# Adafruit_Circuit_Playground_Express.net
KiCad netlist of a schematic drawn in EAGLE
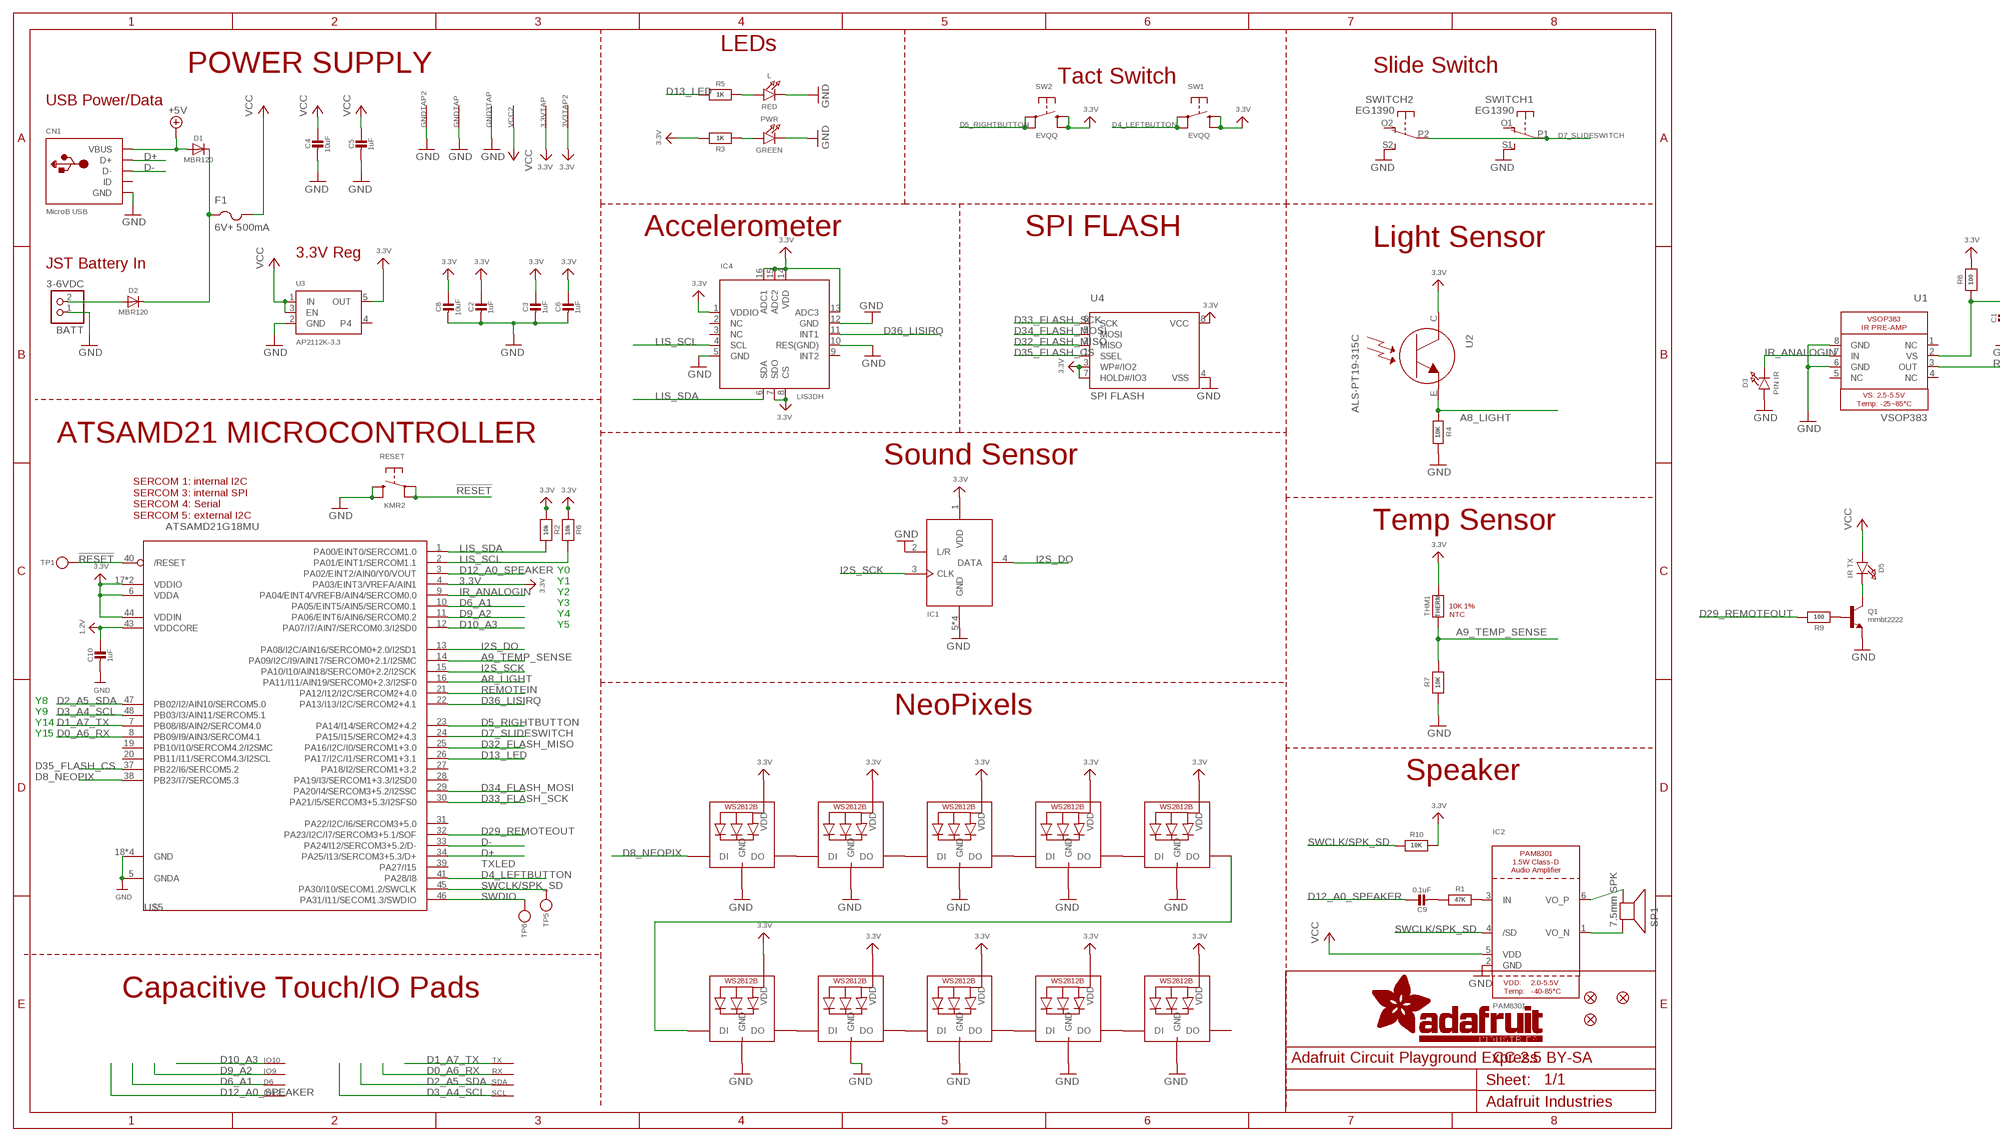
[diagram p0: schematic, sheet 1, part 1 of 2]
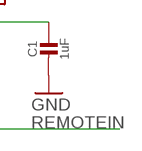
[diagram p1: schematic, sheet 1, part 2 of 2]

(export (version "E")
  (design (tool "Eeschema 10.0.6"))
  (components
    (comp (ref "3.3VTAP")
      (value "SEWTAP-ALLIGATOR")
      (footprint "eagle-import:SEWALLI")
      (libsource (lib "eagle-import") (part "SEWTAP-ALLIGATOR"))
    )
    (comp (ref "3V3TAP2")
      (value "SEWTAP-ALLIGATOR")
      (footprint "eagle-import:SEWALLI")
      (libsource (lib "eagle-import") (part "SEWTAP-ALLIGATOR"))
    )
    (comp (ref "BATT")
      (value "3-6VDC")
      (footprint "eagle-import:JSTPH2")
      (libsource (lib "eagle-import") (part "CON_JST_PH_2PIN"))
    )
    (comp (ref "C1")
      (value "1uF")
      (footprint "eagle-import:0603-NO")
      (libsource (lib "eagle-import") (part "CAP_CERAMIC0603_NO"))
    )
    (comp (ref "C2")
      (value "1uF")
      (footprint "eagle-import:0603-NO")
      (libsource (lib "eagle-import") (part "CAP_CERAMIC0603_NO"))
    )
    (comp (ref "C3")
      (value "1uF")
      (footprint "eagle-import:0603-NO")
      (libsource (lib "eagle-import") (part "CAP_CERAMIC0603_NO"))
    )
    (comp (ref "C4")
      (value "10uF")
      (footprint "eagle-import:0805-NO")
      (libsource (lib "eagle-import") (part "CAP_CERAMIC0805-NOOUTLINE"))
    )
    (comp (ref "C5")
      (value "1uF")
      (footprint "eagle-import:0603-NO")
      (libsource (lib "eagle-import") (part "CAP_CERAMIC0603_NO"))
    )
    (comp (ref "C6")
      (value "1uF")
      (footprint "eagle-import:0603-NO")
      (libsource (lib "eagle-import") (part "CAP_CERAMIC0603_NO"))
    )
    (comp (ref "C8")
      (value "10uF")
      (footprint "eagle-import:0805-NO")
      (libsource (lib "eagle-import") (part "CAP_CERAMIC0805-NOOUTLINE"))
    )
    (comp (ref "C9")
      (value "0.1uF")
      (footprint "eagle-import:0603-NO")
      (libsource (lib "eagle-import") (part "CAP_CERAMIC0603_NO"))
    )
    (comp (ref "C10")
      (value "1uF")
      (footprint "eagle-import:0603-NO")
      (libsource (lib "eagle-import") (part "CAP_CERAMIC0603_NO"))
    )
    (comp (ref "CN1")
      (value "MicroB USB")
      (footprint "eagle-import:4UCONN_20329_V2")
      (libsource (lib "eagle-import") (part "USB_MICRO_20329_V2"))
    )
    (comp (ref "D1")
      (value "MBR120")
      (footprint "eagle-import:SOD-123")
      (libsource (lib "eagle-import") (part "DIODESOD-123"))
    )
    (comp (ref "D2")
      (value "MBR120")
      (footprint "eagle-import:SOD-123")
      (libsource (lib "eagle-import") (part "DIODESOD-123"))
    )
    (comp (ref "D3")
      (value "PIN IR")
      (footprint "eagle-import:CHIPLED_1206_NOOUTLINE")
      (libsource (lib "eagle-import") (part "LED1206_NOOUTLINE"))
    )
    (comp (ref "D5")
      (value "IR TX")
      (footprint "eagle-import:CHIPLED_1206_NOOUTLINE")
      (libsource (lib "eagle-import") (part "LED1206_NOOUTLINE"))
    )
    (comp (ref "D6")
      (value "SEWTAP-ALLIGATOR")
      (footprint "eagle-import:SEWALLI")
      (libsource (lib "eagle-import") (part "SEWTAP-ALLIGATOR"))
    )
    (comp (ref "F1")
      (value "6V+ 500mA")
      (footprint "eagle-import:R1206")
      (libsource (lib "eagle-import") (part "PTCFUSE-1206"))
    )
    (comp (ref "GND3TAP")
      (value "SEWTAP-ALLIGATOR")
      (footprint "eagle-import:SEWALLI")
      (libsource (lib "eagle-import") (part "SEWTAP-ALLIGATOR"))
    )
    (comp (ref "GNDTAP")
      (value "SEWTAP-ALLIGATOR")
      (footprint "eagle-import:SEWALLI")
      (libsource (lib "eagle-import") (part "SEWTAP-ALLIGATOR"))
    )
    (comp (ref "GNDTAP2")
      (value "SEWTAP-ALLIGATOR")
      (footprint "eagle-import:SEWALLI")
      (libsource (lib "eagle-import") (part "SEWTAP-ALLIGATOR"))
    )
    (comp (ref "IC1")
      (value "MIC_PDM")
      (footprint "eagle-import:SPK0415HM4H")
      (libsource (lib "eagle-import") (part "MIC_PDM_SPK0415"))
    )
    (comp (ref "IC2")
      (value "PAM8301")
      (footprint "eagle-import:SOT23-6")
      (libsource (lib "eagle-import") (part "PAM8301"))
    )
    (comp (ref "IC4")
      (value "LIS3DH")
      (footprint "eagle-import:LGA16_3X3MM")
      (libsource (lib "eagle-import") (part "ACCEL_LIS3DHTR"))
    )
    (comp (ref "IO9")
      (value "SEWTAP-ALLIGATOR")
      (footprint "eagle-import:SEWALLI")
      (libsource (lib "eagle-import") (part "SEWTAP-ALLIGATOR"))
    )
    (comp (ref "IO10")
      (value "SEWTAP-ALLIGATOR")
      (footprint "eagle-import:SEWALLI")
      (libsource (lib "eagle-import") (part "SEWTAP-ALLIGATOR"))
    )
    (comp (ref "IO12")
      (value "SEWTAP-ALLIGATOR")
      (footprint "eagle-import:SEWALLI")
      (libsource (lib "eagle-import") (part "SEWTAP-ALLIGATOR"))
    )
    (comp (ref "L")
      (value "RED")
      (footprint "eagle-import:CHIPLED_0805_NOOUTLINE")
      (libsource (lib "eagle-import") (part "LED0805_NOOUTLINE"))
    )
    (comp (ref "LED1")
      (value "WS2812B3535")
      (footprint "eagle-import:LED3535")
      (libsource (lib "eagle-import") (part "WS2812B3535"))
    )
    (comp (ref "LED2")
      (value "WS2812B3535")
      (footprint "eagle-import:LED3535")
      (libsource (lib "eagle-import") (part "WS2812B3535"))
    )
    (comp (ref "LED3")
      (value "WS2812B3535")
      (footprint "eagle-import:LED3535")
      (libsource (lib "eagle-import") (part "WS2812B3535"))
    )
    (comp (ref "LED4")
      (value "WS2812B3535")
      (footprint "eagle-import:LED3535")
      (libsource (lib "eagle-import") (part "WS2812B3535"))
    )
    (comp (ref "LED5")
      (value "WS2812B3535")
      (footprint "eagle-import:LED3535")
      (libsource (lib "eagle-import") (part "WS2812B3535"))
    )
    (comp (ref "LED6")
      (value "WS2812B3535")
      (footprint "eagle-import:LED3535")
      (libsource (lib "eagle-import") (part "WS2812B3535"))
    )
    (comp (ref "LED7")
      (value "WS2812B3535")
      (footprint "eagle-import:LED3535")
      (libsource (lib "eagle-import") (part "WS2812B3535"))
    )
    (comp (ref "LED8")
      (value "WS2812B3535")
      (footprint "eagle-import:LED3535")
      (libsource (lib "eagle-import") (part "WS2812B3535"))
    )
    (comp (ref "LED9")
      (value "WS2812B3535")
      (footprint "eagle-import:LED3535")
      (libsource (lib "eagle-import") (part "WS2812B3535"))
    )
    (comp (ref "LED10")
      (value "WS2812B3535")
      (footprint "eagle-import:LED3535")
      (libsource (lib "eagle-import") (part "WS2812B3535"))
    )
    (comp (ref "PWR")
      (value "GREEN")
      (footprint "eagle-import:CHIPLED_0805_NOOUTLINE")
      (libsource (lib "eagle-import") (part "LED0805_NOOUTLINE"))
    )
    (comp (ref "Q1")
      (value "mmbt2222")
      (footprint "eagle-import:SOT23-R")
      (libsource (lib "eagle-import") (part "TRANSISTOR_NPN"))
    )
    (comp (ref "R1")
      (value "47K")
      (footprint "eagle-import:0603-NO")
      (libsource (lib "eagle-import") (part "RESISTOR_0603_NOOUT"))
    )
    (comp (ref "R2")
      (value "10k")
      (footprint "eagle-import:0603-NO")
      (libsource (lib "eagle-import") (part "RESISTOR_0603_NOOUT"))
    )
    (comp (ref "R3")
      (value "1K")
      (footprint "eagle-import:0603-NO")
      (libsource (lib "eagle-import") (part "RESISTOR_0603_NOOUT"))
    )
    (comp (ref "R4")
      (value "10K")
      (footprint "eagle-import:0603-NO")
      (libsource (lib "eagle-import") (part "RESISTOR_0603_NOOUT"))
    )
    (comp (ref "R5")
      (value "1K")
      (footprint "eagle-import:0603-NO")
      (libsource (lib "eagle-import") (part "RESISTOR_0603_NOOUT"))
    )
    (comp (ref "R6")
      (value "10k")
      (footprint "eagle-import:0603-NO")
      (libsource (lib "eagle-import") (part "RESISTOR_0603_NOOUT"))
    )
    (comp (ref "R7")
      (value "10K")
      (footprint "eagle-import:0603-NO")
      (libsource (lib "eagle-import") (part "RESISTOR_0603_NOOUT"))
    )
    (comp (ref "R8")
      (value "100")
      (footprint "eagle-import:0603-NO")
      (libsource (lib "eagle-import") (part "RESISTOR_0603_NOOUT"))
    )
    (comp (ref "R9")
      (value "100")
      (footprint "eagle-import:0603-NO")
      (libsource (lib "eagle-import") (part "RESISTOR_0603_NOOUT"))
    )
    (comp (ref "R10")
      (value "10K")
      (footprint "eagle-import:0603-NO")
      (libsource (lib "eagle-import") (part "RESISTOR_0603_NOOUT"))
    )
    (comp (ref "RESET")
      (value "KMR2")
      (footprint "eagle-import:BTN_KMR2_4.6X2.8")
      (libsource (lib "eagle-import") (part "SWITCH_TACT_SMT4.6X2.8"))
    )
    (comp (ref "RX")
      (value "SEWTAP-ALLIGATOR")
      (footprint "eagle-import:SEWALLI")
      (libsource (lib "eagle-import") (part "SEWTAP-ALLIGATOR"))
    )
    (comp (ref "SCL")
      (value "SEWTAP-ALLIGATOR")
      (footprint "eagle-import:SEWALLI")
      (libsource (lib "eagle-import") (part "SEWTAP-ALLIGATOR"))
    )
    (comp (ref "SDA")
      (value "SEWTAP-ALLIGATOR")
      (footprint "eagle-import:SEWALLI")
      (libsource (lib "eagle-import") (part "SEWTAP-ALLIGATOR"))
    )
    (comp (ref "SP1")
      (value "7.5mm SPK")
      (footprint "eagle-import:BUZZER_SMT_7.5MM")
      (libsource (lib "eagle-import") (part "SPEAKER_7.5MM"))
    )
    (comp (ref "SW1")
      (value "EVQQ")
      (footprint "eagle-import:EVQ-Q2_SMALLER")
      (libsource (lib "eagle-import") (part "SWITCH_TACT_SMT_EVQQ2_SMALL"))
    )
    (comp (ref "SW2")
      (value "EVQQ")
      (footprint "eagle-import:EVQ-Q2_SMALLER")
      (libsource (lib "eagle-import") (part "SWITCH_TACT_SMT_EVQQ2_SMALL"))
    )
    (comp (ref "SWITCH")
      (value "EG1390")
      (footprint "eagle-import:EG1390")
      (libsource (lib "eagle-import") (part "DPDT-EG1390"))
    )
    (comp (ref "THM1")
      (value "THERM")
      (footprint "eagle-import:_0402")
      (libsource (lib "eagle-import") (part "RESISTOR_0402"))
    )
    (comp (ref "TP1")
      (value "TESTPOINTROUND1.5MM")
      (footprint "eagle-import:TESTPOINT_ROUND_1.5MM")
      (libsource (lib "eagle-import") (part "TESTPOINTROUND1.5MM"))
    )
    (comp (ref "TP5")
      (value "TESTPOINTROUND1.5MM")
      (footprint "eagle-import:TESTPOINT_ROUND_1.5MM")
      (libsource (lib "eagle-import") (part "TESTPOINTROUND1.5MM"))
    )
    (comp (ref "TP6")
      (value "TESTPOINTROUND1.5MM")
      (footprint "eagle-import:TESTPOINT_ROUND_1.5MM")
      (libsource (lib "eagle-import") (part "TESTPOINTROUND1.5MM"))
    )
    (comp (ref "TX")
      (value "SEWTAP-ALLIGATOR")
      (footprint "eagle-import:SEWALLI")
      (libsource (lib "eagle-import") (part "SEWTAP-ALLIGATOR"))
    )
    (comp (ref "U$2")
      (value "FIDUCIAL_1MM")
      (footprint "eagle-import:FIDUCIAL_1MM")
      (libsource (lib "eagle-import") (part "FIDUCIAL_1MM"))
    )
    (comp (ref "U$3")
      (value "FIDUCIAL_1MM")
      (footprint "eagle-import:FIDUCIAL_1MM")
      (fields (field (name "BOM") "EXCLUDE"))
      (libsource (lib "eagle-import") (part "FIDUCIAL_1MM"))
    )
    (comp (ref "U$5")
      (value "ATSAMD21G18MU")
      (footprint "eagle-import:TQFN48_7MM")
      (libsource (lib "eagle-import") (part "ATSAMD21G_QFN"))
    )
    (comp (ref "U$6")
      (value "FIDUCIAL_1MM")
      (footprint "eagle-import:FIDUCIAL_1MM")
      (libsource (lib "eagle-import") (part "FIDUCIAL_1MM"))
    )
    (comp (ref "U1")
      (value "VSOP383")
      (footprint "eagle-import:VSOP383")
      (libsource (lib "eagle-import") (part "VSOP383"))
    )
    (comp (ref "U2")
      (value "ALS-PT19-315C")
      (footprint "eagle-import:ALS-PT19-315C")
      (libsource (lib "eagle-import") (part "LIGHT_ALS-PT19-315C"))
    )
    (comp (ref "U3")
      (value "AP2112K-3.3")
      (footprint "eagle-import:SOT23-5")
      (libsource (lib "eagle-import") (part "VREG_SOT23-5"))
    )
    (comp (ref "U4")
      (value "SPI FLASH")
      (footprint "eagle-import:SOIC8_150MIL")
      (libsource (lib "eagle-import") (part "SPIFLASH_SOIC8"))
    )
    (comp (ref "VCC2")
      (value "SEWTAP-ALLIGATOR")
      (footprint "eagle-import:SEWALLI")
      (libsource (lib "eagle-import") (part "SEWTAP-ALLIGATOR"))
    )
  )
  (nets
    (net (code "1") (name "+5V") (class "Default")
      (node (ref "CN1") (pin "VBUS") (pinfunction "VBUS_VBUS") (pintype "power_in"))
      (node (ref "D1") (pin "A") (pinfunction "A_A") (pintype "passive"))
    )
    (net (code "2") (name "/A8_LIGHT") (class "Default")
      (node (ref "R4") (pin "2") (pinfunction "2_2") (pintype "passive"))
      (node (ref "U$5") (pin "16") (pinfunction "PA11/I11/AIN19/SERCOM0+2.3/I2SF0_16") (pintype "bidirectional"))
      (node (ref "U2") (pin "E") (pinfunction "E_E") (pintype "bidirectional"))
    )
    (net (code "3") (name "/A9_TEMP_SENSE") (class "Default")
      (node (ref "R7") (pin "2") (pinfunction "2_2") (pintype "passive"))
      (node (ref "THM1") (pin "1") (pinfunction "1_1") (pintype "passive"))
      (node (ref "U$5") (pin "14") (pinfunction "PA09/I2C/I9/AIN17/SERCOM0+2.1/I2SMC_14") (pintype "bidirectional"))
    )
    (net (code "4") (name "/D+") (class "Default")
      (node (ref "CN1") (pin "D+") (pinfunction "D+_D+") (pintype "bidirectional"))
      (node (ref "U$5") (pin "34") (pinfunction "PA25/I13/SERCOM3+5.3/D+_34") (pintype "bidirectional"))
    )
    (net (code "5") (name "/D-") (class "Default")
      (node (ref "CN1") (pin "D-") (pinfunction "D-_D-") (pintype "bidirectional"))
      (node (ref "U$5") (pin "33") (pinfunction "PA24/I12/SERCOM3+5.2/D-_33") (pintype "bidirectional"))
    )
    (net (code "6") (name "/D0_A6_RX") (class "Default")
      (node (ref "RX") (pin "P$1") (pinfunction "SEW_P$1") (pintype "bidirectional"))
      (node (ref "U$5") (pin "8") (pinfunction "PB09/I9/AIN3/SERCOM4.1_8") (pintype "bidirectional"))
    )
    (net (code "7") (name "/D1_A7_TX") (class "Default")
      (node (ref "TX") (pin "P$1") (pinfunction "SEW_P$1") (pintype "bidirectional"))
      (node (ref "U$5") (pin "7") (pinfunction "PB08/I8/AIN2/SERCOM4.0_7") (pintype "bidirectional"))
    )
    (net (code "8") (name "/D2_A5_SDA") (class "Default")
      (node (ref "SDA") (pin "P$1") (pinfunction "SEW_P$1") (pintype "bidirectional"))
      (node (ref "U$5") (pin "47") (pinfunction "PB02/I2/AIN10/SERCOM5.0_47") (pintype "bidirectional"))
    )
    (net (code "9") (name "/D3_A4_SCL") (class "Default")
      (node (ref "SCL") (pin "P$1") (pinfunction "SEW_P$1") (pintype "bidirectional"))
      (node (ref "U$5") (pin "48") (pinfunction "PB03/I3/AIN11/SERCOM5.1_48") (pintype "bidirectional"))
    )
    (net (code "10") (name "/D4_LEFTBUTTON") (class "Default")
      (node (ref "SW1") (pin "A") (pinfunction "P_A") (pintype "passive"))
      (node (ref "SW1") (pin "A'") (pinfunction "P1_A'") (pintype "passive"))
      (node (ref "U$5") (pin "41") (pinfunction "PA28/I8_41") (pintype "bidirectional"))
    )
    (net (code "11") (name "/D5_RIGHTBUTTON") (class "Default")
      (node (ref "SW2") (pin "A") (pinfunction "P_A") (pintype "passive"))
      (node (ref "SW2") (pin "A'") (pinfunction "P1_A'") (pintype "passive"))
      (node (ref "U$5") (pin "23") (pinfunction "PA14/I14/SERCOM2+4.2_23") (pintype "bidirectional"))
    )
    (net (code "12") (name "/D6_A1") (class "Default")
      (node (ref "D6") (pin "P$1") (pinfunction "SEW_P$1") (pintype "bidirectional"))
      (node (ref "U$5") (pin "10") (pinfunction "PA05/EINT5/AIN5/SERCOM0.1_10") (pintype "bidirectional"))
    )
    (net (code "13") (name "/D7_SLIDESWITCH") (class "Default")
      (node (ref "SWITCH") (pin "P1") (pinfunction "P_P1") (pintype "passive"))
      (node (ref "SWITCH") (pin "P2") (pinfunction "P_P2") (pintype "passive"))
      (node (ref "U$5") (pin "24") (pinfunction "PA15/I15/SERCOM2+4.3_24") (pintype "bidirectional"))
    )
    (net (code "14") (name "/D8_NEOPIX") (class "Default")
      (node (ref "LED6") (pin "1") (pinfunction "DI_1") (pintype "input"))
      (node (ref "U$5") (pin "38") (pinfunction "PB23/I7/SERCOM5.3_38") (pintype "bidirectional"))
    )
    (net (code "15") (name "/D9_A2") (class "Default")
      (node (ref "IO9") (pin "P$1") (pinfunction "SEW_P$1") (pintype "bidirectional"))
      (node (ref "U$5") (pin "11") (pinfunction "PA06/EINT6/AIN6/SERCOM0.2_11") (pintype "bidirectional"))
    )
    (net (code "16") (name "/D10_A3") (class "Default")
      (node (ref "IO10") (pin "P$1") (pinfunction "SEW_P$1") (pintype "bidirectional"))
      (node (ref "U$5") (pin "12") (pinfunction "PA07/I7/AIN7/SERCOM0.3/I2SD0_12") (pintype "bidirectional"))
    )
    (net (code "17") (name "/D12_A0_SPEAKER") (class "Default")
      (node (ref "C9") (pin "1") (pinfunction "1_1") (pintype "passive"))
      (node (ref "IO12") (pin "P$1") (pinfunction "SEW_P$1") (pintype "bidirectional"))
      (node (ref "U$5") (pin "3") (pinfunction "PA02/EINT2/AIN0/Y0/VOUT_3") (pintype "bidirectional"))
    )
    (net (code "18") (name "/D13_LED") (class "Default")
      (node (ref "R5") (pin "1") (pinfunction "1_1") (pintype "passive"))
      (node (ref "U$5") (pin "26") (pinfunction "PA17/I2C/I1/SERCOM1+3.1_26") (pintype "bidirectional"))
    )
    (net (code "19") (name "/D29_REMOTEOUT") (class "Default")
      (node (ref "R9") (pin "2") (pinfunction "2_2") (pintype "passive"))
      (node (ref "U$5") (pin "32") (pinfunction "PA23/I2C/I7/SERCOM3+5.1/SOF_32") (pintype "bidirectional"))
    )
    (net (code "20") (name "/D32_FLASH_MISO") (class "Default")
      (node (ref "U$5") (pin "25") (pinfunction "PA16/I2C/I0/SERCOM1+3.0_25") (pintype "bidirectional"))
      (node (ref "U4") (pin "2") (pinfunction "MISO_2") (pintype "bidirectional"))
    )
    (net (code "21") (name "/D33_FLASH_SCK") (class "Default")
      (node (ref "U$5") (pin "30") (pinfunction "PA21/I5/SERCOM3+5.3/I2SFS0_30") (pintype "bidirectional"))
      (node (ref "U4") (pin "6") (pinfunction "SCK_6") (pintype "bidirectional"))
    )
    (net (code "22") (name "/D34_FLASH_MOSI") (class "Default")
      (node (ref "U$5") (pin "29") (pinfunction "PA20/I4/SERCOM3+5.2/I2SSC_29") (pintype "bidirectional"))
      (node (ref "U4") (pin "5") (pinfunction "MOSI_5") (pintype "bidirectional"))
    )
    (net (code "23") (name "/D35_FLASH_CS") (class "Default")
      (node (ref "U$5") (pin "37") (pinfunction "PB22/I6/SERCOM5.2_37") (pintype "bidirectional"))
      (node (ref "U4") (pin "1") (pinfunction "SSEL_1") (pintype "bidirectional"))
    )
    (net (code "24") (name "/D36_LISIRQ") (class "Default")
      (node (ref "IC4") (pin "11") (pinfunction "INT1_11") (pintype "output"))
      (node (ref "U$5") (pin "22") (pinfunction "PA13/I13/I2C/SERCOM2+4.1_22") (pintype "bidirectional"))
    )
    (net (code "25") (name "/I2S_DO") (class "Default")
      (node (ref "IC1") (pin "4") (pinfunction "DATA_4") (pintype "bidirectional"))
      (node (ref "U$5") (pin "13") (pinfunction "PA08/I2C/AIN16/SERCOM0+2.0/I2SD1_13") (pintype "bidirectional"))
    )
    (net (code "26") (name "/I2S_SCK") (class "Default")
      (node (ref "IC1") (pin "3") (pinfunction "CLK_3") (pintype "input"))
      (node (ref "U$5") (pin "15") (pinfunction "PA10/I10/AIN18/SERCOM0+2.2/I2SCK_15") (pintype "bidirectional"))
    )
    (net (code "27") (name "/IR_ANALOGIN") (class "Default")
      (node (ref "D3") (pin "C") (pinfunction "C_C") (pintype "passive"))
      (node (ref "U$5") (pin "9") (pinfunction "PA04/EINT4/VREFB/AIN4/SERCOM0.0_9") (pintype "bidirectional"))
      (node (ref "U1") (pin "7") (pinfunction "IN_7") (pintype "input"))
    )
    (net (code "28") (name "/LIS_SCL") (class "Default")
      (node (ref "IC4") (pin "4") (pinfunction "SCL_4") (pintype "bidirectional"))
      (node (ref "R6") (pin "2") (pinfunction "2_2") (pintype "passive"))
      (node (ref "U$5") (pin "2") (pinfunction "PA01/EINT1/SERCOM1.1_2") (pintype "bidirectional"))
    )
    (net (code "29") (name "/LIS_SDA") (class "Default")
      (node (ref "IC4") (pin "6") (pinfunction "SDA_6") (pintype "bidirectional"))
      (node (ref "R2") (pin "2") (pinfunction "2_2") (pintype "passive"))
      (node (ref "U$5") (pin "1") (pinfunction "PA00/EINT0/SERCOM1.0_1") (pintype "bidirectional"))
    )
    (net (code "30") (name "/REMOTEIN") (class "Default")
      (node (ref "U$5") (pin "21") (pinfunction "PA12/I12/I2C/SERCOM2+4.0_21") (pintype "bidirectional"))
      (node (ref "U1") (pin "3") (pinfunction "OUT_3") (pintype "output"))
    )
    (net (code "31") (name "/SWCLK{slash}SPK_SD") (class "Default")
      (node (ref "IC2") (pin "4") (pinfunction "/SD_4") (pintype "input"))
      (node (ref "R10") (pin "1") (pinfunction "1_1") (pintype "passive"))
      (node (ref "TP5") (pin "P$1") (pinfunction "P$1_P$1") (pintype "bidirectional"))
      (node (ref "U$5") (pin "45") (pinfunction "PA30/I10/SECOM1.2/SWCLK_45") (pintype "bidirectional"))
    )
    (net (code "32") (name "/SWDIO") (class "Default")
      (node (ref "TP6") (pin "P$1") (pinfunction "P$1_P$1") (pintype "bidirectional"))
      (node (ref "U$5") (pin "46") (pinfunction "PA31/I11/SECOM1.3/SWDIO_46") (pintype "bidirectional"))
    )
    (net (code "33") (name "/~{RESET}") (class "Default")
      (node (ref "RESET") (pin "A") (pinfunction "P_A") (pintype "passive"))
      (node (ref "RESET") (pin "A'") (pinfunction "P1_A'") (pintype "passive"))
      (node (ref "TP1") (pin "P$1") (pinfunction "P$1_P$1") (pintype "bidirectional"))
      (node (ref "U$5") (pin "40") (pinfunction "/RESET_40") (pintype "bidirectional"))
    )
    (net (code "34") (name "1.2V") (class "Default")
      (node (ref "C10") (pin "1") (pinfunction "1_1") (pintype "passive"))
      (node (ref "U$5") (pin "43") (pinfunction "VDDCORE_43") (pintype "power_in"))
    )
    (net (code "35") (name "3.3V") (class "Default")
      (node (ref "3.3VTAP") (pin "P$1") (pinfunction "SEW_P$1") (pintype "bidirectional"))
      (node (ref "3V3TAP2") (pin "P$1") (pinfunction "SEW_P$1") (pintype "bidirectional"))
      (node (ref "C2") (pin "1") (pinfunction "1_1") (pintype "passive"))
      (node (ref "C3") (pin "1") (pinfunction "1_1") (pintype "passive"))
      (node (ref "C6") (pin "1") (pinfunction "1_1") (pintype "passive"))
      (node (ref "C8") (pin "1") (pinfunction "1_1") (pintype "passive"))
      (node (ref "IC1") (pin "1") (pinfunction "VDD_1") (pintype "power_in"))
      (node (ref "IC4") (pin "1") (pinfunction "VDDIO_1") (pintype "power_in"))
      (node (ref "IC4") (pin "13") (pinfunction "ADC3_13") (pintype "input"))
      (node (ref "IC4") (pin "14") (pinfunction "VDD_14") (pintype "power_in"))
      (node (ref "IC4") (pin "15") (pinfunction "ADC2_15") (pintype "input"))
      (node (ref "IC4") (pin "16") (pinfunction "ADC1_16") (pintype "input"))
      (node (ref "IC4") (pin "7") (pinfunction "SDO_7") (pintype "bidirectional"))
      (node (ref "IC4") (pin "8") (pinfunction "CS_8") (pintype "input"))
      (node (ref "LED1") (pin "2") (pinfunction "VDD_2") (pintype "power_in"))
      (node (ref "LED10") (pin "2") (pinfunction "VDD_2") (pintype "power_in"))
      (node (ref "LED2") (pin "2") (pinfunction "VDD_2") (pintype "power_in"))
      (node (ref "LED3") (pin "2") (pinfunction "VDD_2") (pintype "power_in"))
      (node (ref "LED4") (pin "2") (pinfunction "VDD_2") (pintype "power_in"))
      (node (ref "LED5") (pin "2") (pinfunction "VDD_2") (pintype "power_in"))
      (node (ref "LED6") (pin "2") (pinfunction "VDD_2") (pintype "power_in"))
      (node (ref "LED7") (pin "2") (pinfunction "VDD_2") (pintype "power_in"))
      (node (ref "LED8") (pin "2") (pinfunction "VDD_2") (pintype "power_in"))
      (node (ref "LED9") (pin "2") (pinfunction "VDD_2") (pintype "power_in"))
      (node (ref "R10") (pin "2") (pinfunction "2_2") (pintype "passive"))
      (node (ref "R2") (pin "1") (pinfunction "1_1") (pintype "passive"))
      (node (ref "R3") (pin "2") (pinfunction "2_2") (pintype "passive"))
      (node (ref "R6") (pin "1") (pinfunction "1_1") (pintype "passive"))
      (node (ref "R8") (pin "2") (pinfunction "2_2") (pintype "passive"))
      (node (ref "SW1") (pin "B") (pinfunction "S_B") (pintype "passive"))
      (node (ref "SW1") (pin "B'") (pinfunction "S1_B'") (pintype "passive"))
      (node (ref "SW2") (pin "B") (pinfunction "S_B") (pintype "passive"))
      (node (ref "SW2") (pin "B'") (pinfunction "S1_B'") (pintype "passive"))
      (node (ref "THM1") (pin "2") (pinfunction "2_2") (pintype "passive"))
      (node (ref "U$5") (pin "17") (pinfunction "VDDIO_17") (pintype "power_in"))
      (node (ref "U$5") (pin "36") (pinfunction "VDDIO_36") (pintype "power_in"))
      (node (ref "U$5") (pin "4") (pinfunction "PA03/EINT3/VREFA/AIN1_4") (pintype "bidirectional"))
      (node (ref "U$5") (pin "44") (pinfunction "VDDIN_44") (pintype "power_in"))
      (node (ref "U$5") (pin "6") (pinfunction "VDDA_6") (pintype "power_in"))
      (node (ref "U2") (pin "C") (pinfunction "C_C") (pintype "bidirectional"))
      (node (ref "U3") (pin "5") (pinfunction "OUT_5") (pintype "power_in"))
      (node (ref "U4") (pin "3") (pinfunction "WP#/IO2_3") (pintype "bidirectional"))
      (node (ref "U4") (pin "7") (pinfunction "HOLD#/IO3_7") (pintype "bidirectional"))
      (node (ref "U4") (pin "8") (pinfunction "VCC_8") (pintype "bidirectional"))
    )
    (net (code "36") (name "GND") (class "Default")
      (node (ref "BATT") (pin "1") (pinfunction "1_1") (pintype "passive"))
      (node (ref "C1") (pin "2") (pinfunction "2_2") (pintype "passive"))
      (node (ref "C10") (pin "2") (pinfunction "2_2") (pintype "passive"))
      (node (ref "C2") (pin "2") (pinfunction "2_2") (pintype "passive"))
      (node (ref "C3") (pin "2") (pinfunction "2_2") (pintype "passive"))
      (node (ref "C4") (pin "2") (pinfunction "2_2") (pintype "passive"))
      (node (ref "C5") (pin "2") (pinfunction "2_2") (pintype "passive"))
      (node (ref "C6") (pin "2") (pinfunction "2_2") (pintype "passive"))
      (node (ref "C8") (pin "2") (pinfunction "2_2") (pintype "passive"))
      (node (ref "CN1") (pin "BASE@1") (pinfunction "GND_BASE@1") (pintype "power_in"))
      (node (ref "CN1") (pin "BASE@2") (pinfunction "GND_BASE@2") (pintype "power_in"))
      (node (ref "CN1") (pin "GND") (pinfunction "GND_GND") (pintype "power_in"))
      (node (ref "CN1") (pin "SPRT@1") (pinfunction "GND_SPRT@1") (pintype "power_in"))
      (node (ref "CN1") (pin "SPRT@2") (pinfunction "GND_SPRT@2") (pintype "power_in"))
      (node (ref "CN1") (pin "SPRT@3") (pinfunction "GND_SPRT@3") (pintype "power_in"))
      (node (ref "CN1") (pin "SPRT@4") (pinfunction "GND_SPRT@4") (pintype "power_in"))
      (node (ref "D3") (pin "A") (pinfunction "A_A") (pintype "passive"))
      (node (ref "GND3TAP") (pin "P$1") (pinfunction "SEW_P$1") (pintype "bidirectional"))
      (node (ref "GNDTAP") (pin "P$1") (pinfunction "SEW_P$1") (pintype "bidirectional"))
      (node (ref "GNDTAP2") (pin "P$1") (pinfunction "SEW_P$1") (pintype "bidirectional"))
      (node (ref "IC1") (pin "2") (pinfunction "L/R_2") (pintype "input"))
      (node (ref "IC1") (pin "5") (pinfunction "GND_5") (pintype "power_in"))
      (node (ref "IC1") (pin "6") (pinfunction "GND_6") (pintype "power_in"))
      (node (ref "IC1") (pin "7") (pinfunction "GND_7") (pintype "power_in"))
      (node (ref "IC1") (pin "8") (pinfunction "GND_8") (pintype "power_in"))
      (node (ref "IC2") (pin "2") (pinfunction "GND_2") (pintype "power_in"))
      (node (ref "IC4") (pin "10") (pinfunction "RES(GND)_10") (pintype "bidirectional"))
      (node (ref "IC4") (pin "12") (pinfunction "GND_12") (pintype "power_in"))
      (node (ref "IC4") (pin "5") (pinfunction "GND_5") (pintype "power_in"))
      (node (ref "L") (pin "C") (pinfunction "C_C") (pintype "passive"))
      (node (ref "LED1") (pin "4") (pinfunction "GND_4") (pintype "power_in"))
      (node (ref "LED10") (pin "4") (pinfunction "GND_4") (pintype "power_in"))
      (node (ref "LED2") (pin "4") (pinfunction "GND_4") (pintype "power_in"))
      (node (ref "LED3") (pin "4") (pinfunction "GND_4") (pintype "power_in"))
      (node (ref "LED4") (pin "4") (pinfunction "GND_4") (pintype "power_in"))
      (node (ref "LED5") (pin "4") (pinfunction "GND_4") (pintype "power_in"))
      (node (ref "LED6") (pin "4") (pinfunction "GND_4") (pintype "power_in"))
      (node (ref "LED7") (pin "4") (pinfunction "GND_4") (pintype "power_in"))
      (node (ref "LED8") (pin "4") (pinfunction "GND_4") (pintype "power_in"))
      (node (ref "LED9") (pin "4") (pinfunction "GND_4") (pintype "power_in"))
      (node (ref "PWR") (pin "C") (pinfunction "C_C") (pintype "passive"))
      (node (ref "Q1") (pin "2") (pinfunction "E_2") (pintype "passive"))
      (node (ref "R4") (pin "1") (pinfunction "1_1") (pintype "passive"))
      (node (ref "R7") (pin "1") (pinfunction "1_1") (pintype "passive"))
      (node (ref "RESET") (pin "B") (pinfunction "S_B") (pintype "passive"))
      (node (ref "RESET") (pin "B'") (pinfunction "S1_B'") (pintype "passive"))
      (node (ref "SWITCH") (pin "S1") (pinfunction "S_S1") (pintype "passive"))
      (node (ref "SWITCH") (pin "S2") (pinfunction "S_S2") (pintype "passive"))
      (node (ref "U$5") (pin "18") (pinfunction "GND_18") (pintype "power_in"))
      (node (ref "U$5") (pin "35") (pinfunction "GND_35") (pintype "power_in"))
      (node (ref "U$5") (pin "42") (pinfunction "GND_42") (pintype "power_in"))
      (node (ref "U$5") (pin "5") (pinfunction "GNDA_5") (pintype "power_in"))
      (node (ref "U$5") (pin "THERMAL") (pinfunction "GND_THERMAL") (pintype "power_in"))
      (node (ref "U1") (pin "6") (pinfunction "GND_6") (pintype "power_in"))
      (node (ref "U1") (pin "8") (pinfunction "GND_8") (pintype "power_in"))
      (node (ref "U3") (pin "2") (pinfunction "GND_2") (pintype "power_in"))
      (node (ref "U4") (pin "4") (pinfunction "VSS_4") (pintype "bidirectional"))
    )
    (net (code "37") (name "Net-(BATT-Pad2)") (class "Default")
      (node (ref "BATT") (pin "2") (pinfunction "2_2") (pintype "passive"))
      (node (ref "D2") (pin "A") (pinfunction "A_A") (pintype "passive"))
    )
    (net (code "38") (name "Net-(C9-Pad2)") (class "Default")
      (node (ref "C9") (pin "2") (pinfunction "2_2") (pintype "passive"))
      (node (ref "R1") (pin "1") (pinfunction "1_1") (pintype "passive"))
    )
    (net (code "39") (name "Net-(D1-PadC)") (class "Default")
      (node (ref "D1") (pin "C") (pinfunction "C_C") (pintype "passive"))
      (node (ref "D2") (pin "C") (pinfunction "C_C") (pintype "passive"))
      (node (ref "F1") (pin "1") (pinfunction "1_1") (pintype "passive"))
    )
    (net (code "40") (name "Net-(IC2-IN)") (class "Default")
      (node (ref "IC2") (pin "3") (pinfunction "IN_3") (pintype "input"))
      (node (ref "R1") (pin "2") (pinfunction "2_2") (pintype "passive"))
    )
    (net (code "41") (name "Net-(IC2-VO_N)") (class "Default")
      (node (ref "IC2") (pin "1") (pinfunction "VO_N_1") (pintype "output"))
      (node (ref "SP1") (pin "+") (pinfunction "+_+") (pintype "passive"))
    )
    (net (code "42") (name "Net-(IC2-VO_P)") (class "Default")
      (node (ref "IC2") (pin "6") (pinfunction "VO_P_6") (pintype "output"))
      (node (ref "SP1") (pin "-") (pinfunction "-_-") (pintype "passive"))
    )
    (net (code "43") (name "Net-(L-PadA)") (class "Default")
      (node (ref "L") (pin "A") (pinfunction "A_A") (pintype "passive"))
      (node (ref "R5") (pin "2") (pinfunction "2_2") (pintype "passive"))
    )
    (net (code "44") (name "Net-(LED1-DI)") (class "Default")
      (node (ref "LED1") (pin "1") (pinfunction "DI_1") (pintype "input"))
      (node (ref "LED2") (pin "3") (pinfunction "DO_3") (pintype "output"))
    )
    (net (code "45") (name "Net-(LED1-DO)") (class "Default")
      (node (ref "LED1") (pin "3") (pinfunction "DO_3") (pintype "output"))
      (node (ref "LED3") (pin "1") (pinfunction "DI_1") (pintype "input"))
    )
    (net (code "46") (name "Net-(LED3-DO)") (class "Default")
      (node (ref "LED3") (pin "3") (pinfunction "DO_3") (pintype "output"))
      (node (ref "LED4") (pin "1") (pinfunction "DI_1") (pintype "input"))
    )
    (net (code "47") (name "Net-(LED4-DO)") (class "Default")
      (node (ref "LED4") (pin "3") (pinfunction "DO_3") (pintype "output"))
      (node (ref "LED5") (pin "1") (pinfunction "DI_1") (pintype "input"))
    )
    (net (code "48") (name "Net-(LED6-DO)") (class "Default")
      (node (ref "LED6") (pin "3") (pinfunction "DO_3") (pintype "output"))
      (node (ref "LED7") (pin "1") (pinfunction "DI_1") (pintype "input"))
    )
    (net (code "49") (name "Net-(LED7-DO)") (class "Default")
      (node (ref "LED7") (pin "3") (pinfunction "DO_3") (pintype "output"))
      (node (ref "LED8") (pin "1") (pinfunction "DI_1") (pintype "input"))
    )
    (net (code "50") (name "Net-(LED8-DO)") (class "Default")
      (node (ref "LED8") (pin "3") (pinfunction "DO_3") (pintype "output"))
      (node (ref "LED9") (pin "1") (pinfunction "DI_1") (pintype "input"))
    )
    (net (code "51") (name "Net-(LED10-DI)") (class "Default")
      (node (ref "LED10") (pin "1") (pinfunction "DI_1") (pintype "input"))
      (node (ref "LED9") (pin "3") (pinfunction "DO_3") (pintype "output"))
    )
    (net (code "52") (name "Net-(LED10-DO)") (class "Default")
      (node (ref "LED10") (pin "3") (pinfunction "DO_3") (pintype "output"))
      (node (ref "LED2") (pin "1") (pinfunction "DI_1") (pintype "input"))
    )
    (net (code "53") (name "Net-(PWR-PadA)") (class "Default")
      (node (ref "PWR") (pin "A") (pinfunction "A_A") (pintype "passive"))
      (node (ref "R3") (pin "1") (pinfunction "1_1") (pintype "passive"))
    )
    (net (code "54") (name "Net-(Q1-B)") (class "Default")
      (node (ref "Q1") (pin "1") (pinfunction "B_1") (pintype "passive"))
      (node (ref "R9") (pin "1") (pinfunction "1_1") (pintype "passive"))
    )
    (net (code "55") (name "Net-(Q1-C)") (class "Default")
      (node (ref "D5") (pin "C") (pinfunction "C_C") (pintype "passive"))
      (node (ref "Q1") (pin "3") (pinfunction "C_3") (pintype "passive"))
    )
    (net (code "56") (name "Net-(U1-VS)") (class "Default")
      (node (ref "C1") (pin "1") (pinfunction "1_1") (pintype "passive"))
      (node (ref "R8") (pin "1") (pinfunction "1_1") (pintype "passive"))
      (node (ref "U1") (pin "2") (pinfunction "VS_2") (pintype "power_in"))
    )
    (net (code "57") (name "VCC") (class "Default")
      (node (ref "C4") (pin "1") (pinfunction "1_1") (pintype "passive"))
      (node (ref "C5") (pin "1") (pinfunction "1_1") (pintype "passive"))
      (node (ref "D5") (pin "A") (pinfunction "A_A") (pintype "passive"))
      (node (ref "F1") (pin "2") (pinfunction "2_2") (pintype "passive"))
      (node (ref "IC2") (pin "5") (pinfunction "VDD_5") (pintype "power_in"))
      (node (ref "U3") (pin "1") (pinfunction "IN_1") (pintype "power_in"))
      (node (ref "U3") (pin "3") (pinfunction "EN_3") (pintype "input"))
      (node (ref "VCC2") (pin "P$1") (pinfunction "SEW_P$1") (pintype "bidirectional"))
    )
    (net (code "58") (name "unconnected-(CN1-PadID)") (class "Default")
      (node (ref "CN1") (pin "ID") (pinfunction "ID_ID") (pintype "bidirectional"))
    )
    (net (code "59") (name "unconnected-(IC4-INT2-Pad9)") (class "Default")
      (node (ref "IC4") (pin "9") (pinfunction "INT2_9") (pintype "output"))
    )
    (net (code "60") (name "unconnected-(IC4-NC-Pad2)") (class "Default")
      (node (ref "IC4") (pin "2") (pinfunction "NC_2") (pintype "no_connect"))
    )
    (net (code "61") (name "unconnected-(IC4-NC-Pad3)") (class "Default")
      (node (ref "IC4") (pin "3") (pinfunction "NC_3") (pintype "no_connect"))
    )
    (net (code "62") (name "unconnected-(LED5-DO-Pad3)") (class "Default")
      (node (ref "LED5") (pin "3") (pinfunction "DO_3") (pintype "output"))
    )
    (net (code "63") (name "unconnected-(SWITCHA-O-PadO1)") (class "Default")
      (node (ref "SWITCH") (pin "O1") (pinfunction "O_O1") (pintype "passive"))
    )
    (net (code "64") (name "unconnected-(SWITCHB-O-PadO2)") (class "Default")
      (node (ref "SWITCH") (pin "O2") (pinfunction "O_O2") (pintype "passive"))
    )
    (net (code "65") (name "unconnected-(U$5-PA18{slash}I2{slash}SERCOM1+3.2-Pad27)") (class "Default")
      (node (ref "U$5") (pin "27") (pinfunction "PA18/I2/SERCOM1+3.2_27") (pintype "bidirectional"))
    )
    (net (code "66") (name "unconnected-(U$5-PA19{slash}I3{slash}SERCOM1+3.3{slash}I2SD0-Pad28)") (class "Default")
      (node (ref "U$5") (pin "28") (pinfunction "PA19/I3/SERCOM1+3.3/I2SD0_28") (pintype "bidirectional"))
    )
    (net (code "67") (name "unconnected-(U$5-PA22{slash}I2C{slash}I6{slash}SERCOM3+5.0-Pad31)") (class "Default")
      (node (ref "U$5") (pin "31") (pinfunction "PA22/I2C/I6/SERCOM3+5.0_31") (pintype "bidirectional"))
    )
    (net (code "68") (name "unconnected-(U$5-PA27{slash}I15-Pad39)") (class "Default")
      (node (ref "U$5") (pin "39") (pinfunction "PA27/I15_39") (pintype "bidirectional"))
    )
    (net (code "69") (name "unconnected-(U$5-PB10{slash}I10{slash}SERCOM4.2{slash}I2SMC-Pad19)") (class "Default")
      (node (ref "U$5") (pin "19") (pinfunction "PB10/I10/SERCOM4.2/I2SMC_19") (pintype "bidirectional"))
    )
    (net (code "70") (name "unconnected-(U$5-PB11{slash}I11{slash}SERCOM4.3{slash}I2SCL-Pad20)") (class "Default")
      (node (ref "U$5") (pin "20") (pinfunction "PB11/I11/SERCOM4.3/I2SCL_20") (pintype "bidirectional"))
    )
    (net (code "71") (name "unconnected-(U1-NC-Pad1)") (class "Default")
      (node (ref "U1") (pin "1") (pinfunction "NC_1") (pintype "no_connect"))
    )
    (net (code "72") (name "unconnected-(U1-NC-Pad4)") (class "Default")
      (node (ref "U1") (pin "4") (pinfunction "NC_4") (pintype "no_connect"))
    )
    (net (code "73") (name "unconnected-(U1-NC-Pad5)") (class "Default")
      (node (ref "U1") (pin "5") (pinfunction "NC_5") (pintype "no_connect"))
    )
    (net (code "74") (name "unconnected-(U3-P4-Pad4)") (class "Default")
      (node (ref "U3") (pin "4") (pinfunction "P4_4") (pintype "bidirectional"))
    )
  )
)
